# odroid_platine_nerdbot.net
KiCad netlist of a schematic drawn in EAGLE
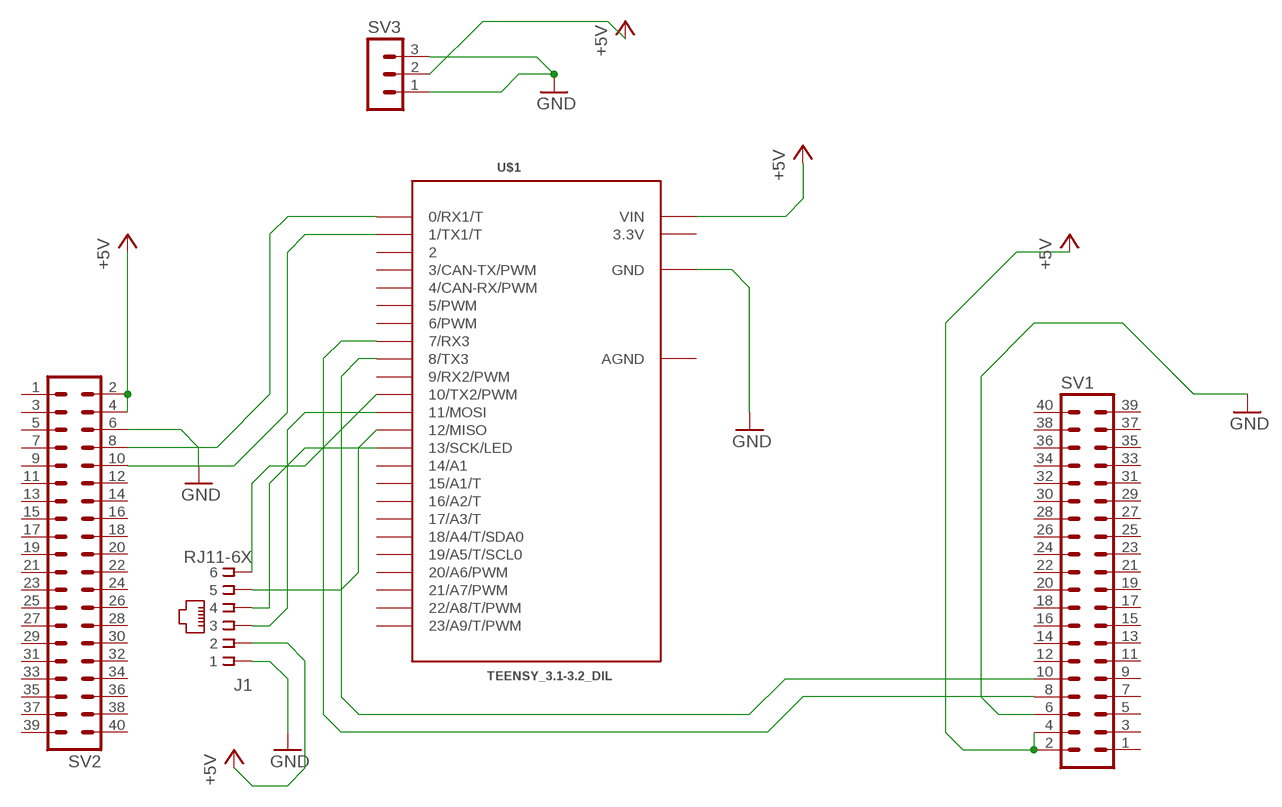
[diagram p0: schematic, sheet 1]

(export (version "E")
  (design (tool "Eeschema 10.0.6"))
  (components
    (comp (ref "J1")
      (value "RJ11-6X")
      (footprint "eagle-import:RJ11-NO_SHIELD")
      (libsource (lib "eagle-import") (part "RJ11-6X"))
    )
    (comp (ref "SV1")
      (value "MA20-2")
      (footprint "eagle-import:MA20-2")
      (libsource (lib "eagle-import") (part "MA20-2"))
    )
    (comp (ref "SV2")
      (value "MA20-2")
      (footprint "eagle-import:MA20-2")
      (libsource (lib "eagle-import") (part "MA20-2"))
    )
    (comp (ref "SV3")
      (value "MA03-1")
      (footprint "eagle-import:MA03-1")
      (libsource (lib "eagle-import") (part "MA03-1"))
    )
    (comp (ref "U$1")
      (value "TEENSY_3.1-3.2_DIL")
      (footprint "eagle-import:TEENSY_3.0-3.2&LC_DIL")
      (libsource (lib "eagle-import") (part "TEENSY_3.1-3.2_DIL"))
    )
  )
  (nets
    (net (code "1") (name "+5V") (class "Default")
      (node (ref "J1") (pin "2") (pinfunction "2_2") (pintype "passive"))
      (node (ref "SV1") (pin "2") (pinfunction "2_2") (pintype "passive"))
      (node (ref "SV1") (pin "4") (pinfunction "4_4") (pintype "passive"))
      (node (ref "SV2") (pin "2") (pinfunction "2_2") (pintype "passive"))
      (node (ref "SV2") (pin "4") (pinfunction "4_4") (pintype "passive"))
      (node (ref "SV3") (pin "2") (pinfunction "2_2") (pintype "passive"))
      (node (ref "U$1") (pin "VIN") (pinfunction "VIN_VIN") (pintype "power_in"))
    )
    (net (code "2") (name "/3.3V") (class "Default")
      (node (ref "U$1") (pin "3.3V") (pinfunction "3.3V_3.3V") (pintype "power_in"))
    )
    (net (code "3") (name "/AGND") (class "Default")
      (node (ref "U$1") (pin "AGND") (pinfunction "AGND_AGND") (pintype "power_in"))
    )
    (net (code "4") (name "GND") (class "Default")
      (node (ref "J1") (pin "1") (pinfunction "1_1") (pintype "passive"))
      (node (ref "SV1") (pin "6") (pinfunction "6_6") (pintype "passive"))
      (node (ref "SV2") (pin "6") (pinfunction "6_6") (pintype "passive"))
      (node (ref "SV3") (pin "1") (pinfunction "1_1") (pintype "passive"))
      (node (ref "SV3") (pin "3") (pinfunction "3_3") (pintype "passive"))
      (node (ref "U$1") (pin "GND") (pinfunction "GND_GND") (pintype "power_in"))
    )
    (net (code "5") (name "Net-(U$1-0{slash}RX1{slash}T)") (class "Default")
      (node (ref "SV2") (pin "8") (pinfunction "8_8") (pintype "passive"))
      (node (ref "U$1") (pin "0") (pinfunction "0/RX1/T_0") (pintype "bidirectional"))
    )
    (net (code "6") (name "Net-(U$1-1{slash}TX1{slash}T)") (class "Default")
      (node (ref "SV2") (pin "10") (pinfunction "10_10") (pintype "passive"))
      (node (ref "U$1") (pin "1") (pinfunction "1/TX1/T_1") (pintype "bidirectional"))
    )
    (net (code "7") (name "Net-(U$1-7{slash}RX3)") (class "Default")
      (node (ref "SV1") (pin "8") (pinfunction "8_8") (pintype "passive"))
      (node (ref "U$1") (pin "7") (pinfunction "7/RX3_7") (pintype "bidirectional"))
    )
    (net (code "8") (name "Net-(U$1-8{slash}TX3)") (class "Default")
      (node (ref "SV1") (pin "10") (pinfunction "10_10") (pintype "passive"))
      (node (ref "U$1") (pin "8") (pinfunction "8/TX3_8") (pintype "bidirectional"))
    )
    (net (code "9") (name "Net-(U$1-10{slash}TX2{slash}PWM)") (class "Default")
      (node (ref "J1") (pin "6") (pinfunction "6_6") (pintype "passive"))
      (node (ref "U$1") (pin "10") (pinfunction "10/TX2/PWM_10") (pintype "bidirectional"))
    )
    (net (code "10") (name "Net-(U$1-11{slash}MOSI)") (class "Default")
      (node (ref "J1") (pin "3") (pinfunction "3_3") (pintype "passive"))
      (node (ref "U$1") (pin "11") (pinfunction "11/MOSI_11") (pintype "bidirectional"))
    )
    (net (code "11") (name "Net-(U$1-12{slash}MISO)") (class "Default")
      (node (ref "J1") (pin "5") (pinfunction "5_5") (pintype "passive"))
      (node (ref "U$1") (pin "12") (pinfunction "12/MISO_12") (pintype "bidirectional"))
    )
    (net (code "12") (name "Net-(U$1-13{slash}SCK{slash}LED)") (class "Default")
      (node (ref "J1") (pin "4") (pinfunction "4_4") (pintype "passive"))
      (node (ref "U$1") (pin "13") (pinfunction "13/SCK/LED_13") (pintype "bidirectional"))
    )
    (net (code "13") (name "unconnected-(SV1-Pad1)") (class "Default")
      (node (ref "SV1") (pin "1") (pinfunction "1_1") (pintype "passive"))
    )
    (net (code "14") (name "unconnected-(SV1-Pad3)") (class "Default")
      (node (ref "SV1") (pin "3") (pinfunction "3_3") (pintype "passive"))
    )
    (net (code "15") (name "unconnected-(SV1-Pad5)") (class "Default")
      (node (ref "SV1") (pin "5") (pinfunction "5_5") (pintype "passive"))
    )
    (net (code "16") (name "unconnected-(SV1-Pad7)") (class "Default")
      (node (ref "SV1") (pin "7") (pinfunction "7_7") (pintype "passive"))
    )
    (net (code "17") (name "unconnected-(SV1-Pad9)") (class "Default")
      (node (ref "SV1") (pin "9") (pinfunction "9_9") (pintype "passive"))
    )
    (net (code "18") (name "unconnected-(SV1-Pad11)") (class "Default")
      (node (ref "SV1") (pin "11") (pinfunction "11_11") (pintype "passive"))
    )
    (net (code "19") (name "unconnected-(SV1-Pad12)") (class "Default")
      (node (ref "SV1") (pin "12") (pinfunction "12_12") (pintype "passive"))
    )
    (net (code "20") (name "unconnected-(SV1-Pad13)") (class "Default")
      (node (ref "SV1") (pin "13") (pinfunction "13_13") (pintype "passive"))
    )
    (net (code "21") (name "unconnected-(SV1-Pad14)") (class "Default")
      (node (ref "SV1") (pin "14") (pinfunction "14_14") (pintype "passive"))
    )
    (net (code "22") (name "unconnected-(SV1-Pad15)") (class "Default")
      (node (ref "SV1") (pin "15") (pinfunction "15_15") (pintype "passive"))
    )
    (net (code "23") (name "unconnected-(SV1-Pad16)") (class "Default")
      (node (ref "SV1") (pin "16") (pinfunction "16_16") (pintype "passive"))
    )
    (net (code "24") (name "unconnected-(SV1-Pad17)") (class "Default")
      (node (ref "SV1") (pin "17") (pinfunction "17_17") (pintype "passive"))
    )
    (net (code "25") (name "unconnected-(SV1-Pad18)") (class "Default")
      (node (ref "SV1") (pin "18") (pinfunction "18_18") (pintype "passive"))
    )
    (net (code "26") (name "unconnected-(SV1-Pad19)") (class "Default")
      (node (ref "SV1") (pin "19") (pinfunction "19_19") (pintype "passive"))
    )
    (net (code "27") (name "unconnected-(SV1-Pad20)") (class "Default")
      (node (ref "SV1") (pin "20") (pinfunction "20_20") (pintype "passive"))
    )
    (net (code "28") (name "unconnected-(SV1-Pad21)") (class "Default")
      (node (ref "SV1") (pin "21") (pinfunction "21_21") (pintype "passive"))
    )
    (net (code "29") (name "unconnected-(SV1-Pad22)") (class "Default")
      (node (ref "SV1") (pin "22") (pinfunction "22_22") (pintype "passive"))
    )
    (net (code "30") (name "unconnected-(SV1-Pad23)") (class "Default")
      (node (ref "SV1") (pin "23") (pinfunction "23_23") (pintype "passive"))
    )
    (net (code "31") (name "unconnected-(SV1-Pad24)") (class "Default")
      (node (ref "SV1") (pin "24") (pinfunction "24_24") (pintype "passive"))
    )
    (net (code "32") (name "unconnected-(SV1-Pad25)") (class "Default")
      (node (ref "SV1") (pin "25") (pinfunction "25_25") (pintype "passive"))
    )
    (net (code "33") (name "unconnected-(SV1-Pad26)") (class "Default")
      (node (ref "SV1") (pin "26") (pinfunction "26_26") (pintype "passive"))
    )
    (net (code "34") (name "unconnected-(SV1-Pad27)") (class "Default")
      (node (ref "SV1") (pin "27") (pinfunction "27_27") (pintype "passive"))
    )
    (net (code "35") (name "unconnected-(SV1-Pad28)") (class "Default")
      (node (ref "SV1") (pin "28") (pinfunction "28_28") (pintype "passive"))
    )
    (net (code "36") (name "unconnected-(SV1-Pad29)") (class "Default")
      (node (ref "SV1") (pin "29") (pinfunction "29_29") (pintype "passive"))
    )
    (net (code "37") (name "unconnected-(SV1-Pad30)") (class "Default")
      (node (ref "SV1") (pin "30") (pinfunction "30_30") (pintype "passive"))
    )
    (net (code "38") (name "unconnected-(SV1-Pad31)") (class "Default")
      (node (ref "SV1") (pin "31") (pinfunction "31_31") (pintype "passive"))
    )
    (net (code "39") (name "unconnected-(SV1-Pad32)") (class "Default")
      (node (ref "SV1") (pin "32") (pinfunction "32_32") (pintype "passive"))
    )
    (net (code "40") (name "unconnected-(SV1-Pad33)") (class "Default")
      (node (ref "SV1") (pin "33") (pinfunction "33_33") (pintype "passive"))
    )
    (net (code "41") (name "unconnected-(SV1-Pad34)") (class "Default")
      (node (ref "SV1") (pin "34") (pinfunction "34_34") (pintype "passive"))
    )
    (net (code "42") (name "unconnected-(SV1-Pad35)") (class "Default")
      (node (ref "SV1") (pin "35") (pinfunction "35_35") (pintype "passive"))
    )
    (net (code "43") (name "unconnected-(SV1-Pad36)") (class "Default")
      (node (ref "SV1") (pin "36") (pinfunction "36_36") (pintype "passive"))
    )
    (net (code "44") (name "unconnected-(SV1-Pad37)") (class "Default")
      (node (ref "SV1") (pin "37") (pinfunction "37_37") (pintype "passive"))
    )
    (net (code "45") (name "unconnected-(SV1-Pad38)") (class "Default")
      (node (ref "SV1") (pin "38") (pinfunction "38_38") (pintype "passive"))
    )
    (net (code "46") (name "unconnected-(SV1-Pad39)") (class "Default")
      (node (ref "SV1") (pin "39") (pinfunction "39_39") (pintype "passive"))
    )
    (net (code "47") (name "unconnected-(SV1-Pad40)") (class "Default")
      (node (ref "SV1") (pin "40") (pinfunction "40_40") (pintype "passive"))
    )
    (net (code "48") (name "unconnected-(SV2-Pad1)") (class "Default")
      (node (ref "SV2") (pin "1") (pinfunction "1_1") (pintype "passive"))
    )
    (net (code "49") (name "unconnected-(SV2-Pad3)") (class "Default")
      (node (ref "SV2") (pin "3") (pinfunction "3_3") (pintype "passive"))
    )
    (net (code "50") (name "unconnected-(SV2-Pad5)") (class "Default")
      (node (ref "SV2") (pin "5") (pinfunction "5_5") (pintype "passive"))
    )
    (net (code "51") (name "unconnected-(SV2-Pad7)") (class "Default")
      (node (ref "SV2") (pin "7") (pinfunction "7_7") (pintype "passive"))
    )
    (net (code "52") (name "unconnected-(SV2-Pad9)") (class "Default")
      (node (ref "SV2") (pin "9") (pinfunction "9_9") (pintype "passive"))
    )
    (net (code "53") (name "unconnected-(SV2-Pad11)") (class "Default")
      (node (ref "SV2") (pin "11") (pinfunction "11_11") (pintype "passive"))
    )
    (net (code "54") (name "unconnected-(SV2-Pad12)") (class "Default")
      (node (ref "SV2") (pin "12") (pinfunction "12_12") (pintype "passive"))
    )
    (net (code "55") (name "unconnected-(SV2-Pad13)") (class "Default")
      (node (ref "SV2") (pin "13") (pinfunction "13_13") (pintype "passive"))
    )
    (net (code "56") (name "unconnected-(SV2-Pad14)") (class "Default")
      (node (ref "SV2") (pin "14") (pinfunction "14_14") (pintype "passive"))
    )
    (net (code "57") (name "unconnected-(SV2-Pad15)") (class "Default")
      (node (ref "SV2") (pin "15") (pinfunction "15_15") (pintype "passive"))
    )
    (net (code "58") (name "unconnected-(SV2-Pad16)") (class "Default")
      (node (ref "SV2") (pin "16") (pinfunction "16_16") (pintype "passive"))
    )
    (net (code "59") (name "unconnected-(SV2-Pad17)") (class "Default")
      (node (ref "SV2") (pin "17") (pinfunction "17_17") (pintype "passive"))
    )
    (net (code "60") (name "unconnected-(SV2-Pad18)") (class "Default")
      (node (ref "SV2") (pin "18") (pinfunction "18_18") (pintype "passive"))
    )
    (net (code "61") (name "unconnected-(SV2-Pad19)") (class "Default")
      (node (ref "SV2") (pin "19") (pinfunction "19_19") (pintype "passive"))
    )
    (net (code "62") (name "unconnected-(SV2-Pad20)") (class "Default")
      (node (ref "SV2") (pin "20") (pinfunction "20_20") (pintype "passive"))
    )
    (net (code "63") (name "unconnected-(SV2-Pad21)") (class "Default")
      (node (ref "SV2") (pin "21") (pinfunction "21_21") (pintype "passive"))
    )
    (net (code "64") (name "unconnected-(SV2-Pad22)") (class "Default")
      (node (ref "SV2") (pin "22") (pinfunction "22_22") (pintype "passive"))
    )
    (net (code "65") (name "unconnected-(SV2-Pad23)") (class "Default")
      (node (ref "SV2") (pin "23") (pinfunction "23_23") (pintype "passive"))
    )
    (net (code "66") (name "unconnected-(SV2-Pad24)") (class "Default")
      (node (ref "SV2") (pin "24") (pinfunction "24_24") (pintype "passive"))
    )
    (net (code "67") (name "unconnected-(SV2-Pad25)") (class "Default")
      (node (ref "SV2") (pin "25") (pinfunction "25_25") (pintype "passive"))
    )
    (net (code "68") (name "unconnected-(SV2-Pad26)") (class "Default")
      (node (ref "SV2") (pin "26") (pinfunction "26_26") (pintype "passive"))
    )
    (net (code "69") (name "unconnected-(SV2-Pad27)") (class "Default")
      (node (ref "SV2") (pin "27") (pinfunction "27_27") (pintype "passive"))
    )
    (net (code "70") (name "unconnected-(SV2-Pad28)") (class "Default")
      (node (ref "SV2") (pin "28") (pinfunction "28_28") (pintype "passive"))
    )
    (net (code "71") (name "unconnected-(SV2-Pad29)") (class "Default")
      (node (ref "SV2") (pin "29") (pinfunction "29_29") (pintype "passive"))
    )
    (net (code "72") (name "unconnected-(SV2-Pad30)") (class "Default")
      (node (ref "SV2") (pin "30") (pinfunction "30_30") (pintype "passive"))
    )
    (net (code "73") (name "unconnected-(SV2-Pad31)") (class "Default")
      (node (ref "SV2") (pin "31") (pinfunction "31_31") (pintype "passive"))
    )
    (net (code "74") (name "unconnected-(SV2-Pad32)") (class "Default")
      (node (ref "SV2") (pin "32") (pinfunction "32_32") (pintype "passive"))
    )
    (net (code "75") (name "unconnected-(SV2-Pad33)") (class "Default")
      (node (ref "SV2") (pin "33") (pinfunction "33_33") (pintype "passive"))
    )
    (net (code "76") (name "unconnected-(SV2-Pad34)") (class "Default")
      (node (ref "SV2") (pin "34") (pinfunction "34_34") (pintype "passive"))
    )
    (net (code "77") (name "unconnected-(SV2-Pad35)") (class "Default")
      (node (ref "SV2") (pin "35") (pinfunction "35_35") (pintype "passive"))
    )
    (net (code "78") (name "unconnected-(SV2-Pad36)") (class "Default")
      (node (ref "SV2") (pin "36") (pinfunction "36_36") (pintype "passive"))
    )
    (net (code "79") (name "unconnected-(SV2-Pad37)") (class "Default")
      (node (ref "SV2") (pin "37") (pinfunction "37_37") (pintype "passive"))
    )
    (net (code "80") (name "unconnected-(SV2-Pad38)") (class "Default")
      (node (ref "SV2") (pin "38") (pinfunction "38_38") (pintype "passive"))
    )
    (net (code "81") (name "unconnected-(SV2-Pad39)") (class "Default")
      (node (ref "SV2") (pin "39") (pinfunction "39_39") (pintype "passive"))
    )
    (net (code "82") (name "unconnected-(SV2-Pad40)") (class "Default")
      (node (ref "SV2") (pin "40") (pinfunction "40_40") (pintype "passive"))
    )
    (net (code "83") (name "unconnected-(U$1-3{slash}CAN-TX{slash}PWM-Pad3)") (class "Default")
      (node (ref "U$1") (pin "3") (pinfunction "3/CAN-TX/PWM_3") (pintype "bidirectional"))
    )
    (net (code "84") (name "unconnected-(U$1-4{slash}CAN-RX{slash}PWM-Pad4)") (class "Default")
      (node (ref "U$1") (pin "4") (pinfunction "4/CAN-RX/PWM_4") (pintype "bidirectional"))
    )
    (net (code "85") (name "unconnected-(U$1-5{slash}PWM-Pad5)") (class "Default")
      (node (ref "U$1") (pin "5") (pinfunction "5/PWM_5") (pintype "bidirectional"))
    )
    (net (code "86") (name "unconnected-(U$1-6{slash}PWM-Pad6)") (class "Default")
      (node (ref "U$1") (pin "6") (pinfunction "6/PWM_6") (pintype "bidirectional"))
    )
    (net (code "87") (name "unconnected-(U$1-9{slash}RX2{slash}PWM-Pad9)") (class "Default")
      (node (ref "U$1") (pin "9") (pinfunction "9/RX2/PWM_9") (pintype "bidirectional"))
    )
    (net (code "88") (name "unconnected-(U$1-14{slash}A1-Pad14{slash}A0)") (class "Default")
      (node (ref "U$1") (pin "14/A0") (pinfunction "14/A1_14/A0") (pintype "bidirectional"))
    )
    (net (code "89") (name "unconnected-(U$1-15{slash}A1{slash}T-Pad15{slash}A1)") (class "Default")
      (node (ref "U$1") (pin "15/A1") (pinfunction "15/A1/T_15/A1") (pintype "bidirectional"))
    )
    (net (code "90") (name "unconnected-(U$1-16{slash}A2{slash}T-Pad16{slash}A2)") (class "Default")
      (node (ref "U$1") (pin "16/A2") (pinfunction "16/A2/T_16/A2") (pintype "bidirectional"))
    )
    (net (code "91") (name "unconnected-(U$1-17{slash}A3{slash}T-Pad17{slash}A3)") (class "Default")
      (node (ref "U$1") (pin "17/A3") (pinfunction "17/A3/T_17/A3") (pintype "bidirectional"))
    )
    (net (code "92") (name "unconnected-(U$1-18{slash}A4{slash}T{slash}SDA0-Pad18{slash}A4)") (class "Default")
      (node (ref "U$1") (pin "18/A4") (pinfunction "18/A4/T/SDA0_18/A4") (pintype "bidirectional"))
    )
    (net (code "93") (name "unconnected-(U$1-19{slash}A5{slash}T{slash}SCL0-Pad19{slash}A5)") (class "Default")
      (node (ref "U$1") (pin "19/A5") (pinfunction "19/A5/T/SCL0_19/A5") (pintype "bidirectional"))
    )
    (net (code "94") (name "unconnected-(U$1-20{slash}A6{slash}PWM-Pad20{slash}A6)") (class "Default")
      (node (ref "U$1") (pin "20/A6") (pinfunction "20/A6/PWM_20/A6") (pintype "bidirectional"))
    )
    (net (code "95") (name "unconnected-(U$1-21{slash}A7{slash}PWM-Pad21{slash}A7)") (class "Default")
      (node (ref "U$1") (pin "21/A7") (pinfunction "21/A7/PWM_21/A7") (pintype "bidirectional"))
    )
    (net (code "96") (name "unconnected-(U$1-22{slash}A8{slash}T{slash}PWM-Pad22{slash}A8)") (class "Default")
      (node (ref "U$1") (pin "22/A8") (pinfunction "22/A8/T/PWM_22/A8") (pintype "bidirectional"))
    )
    (net (code "97") (name "unconnected-(U$1-23{slash}A9{slash}T{slash}PWM-Pad23{slash}A9)") (class "Default")
      (node (ref "U$1") (pin "23/A9") (pinfunction "23/A9/T/PWM_23/A9") (pintype "bidirectional"))
    )
    (net (code "98") (name "unconnected-(U$1-Pad2)") (class "Default")
      (node (ref "U$1") (pin "2") (pinfunction "2_2") (pintype "bidirectional"))
    )
  )
)
